# MCU_Core.net
KiCad netlist of a schematic drawn in Altium Designer
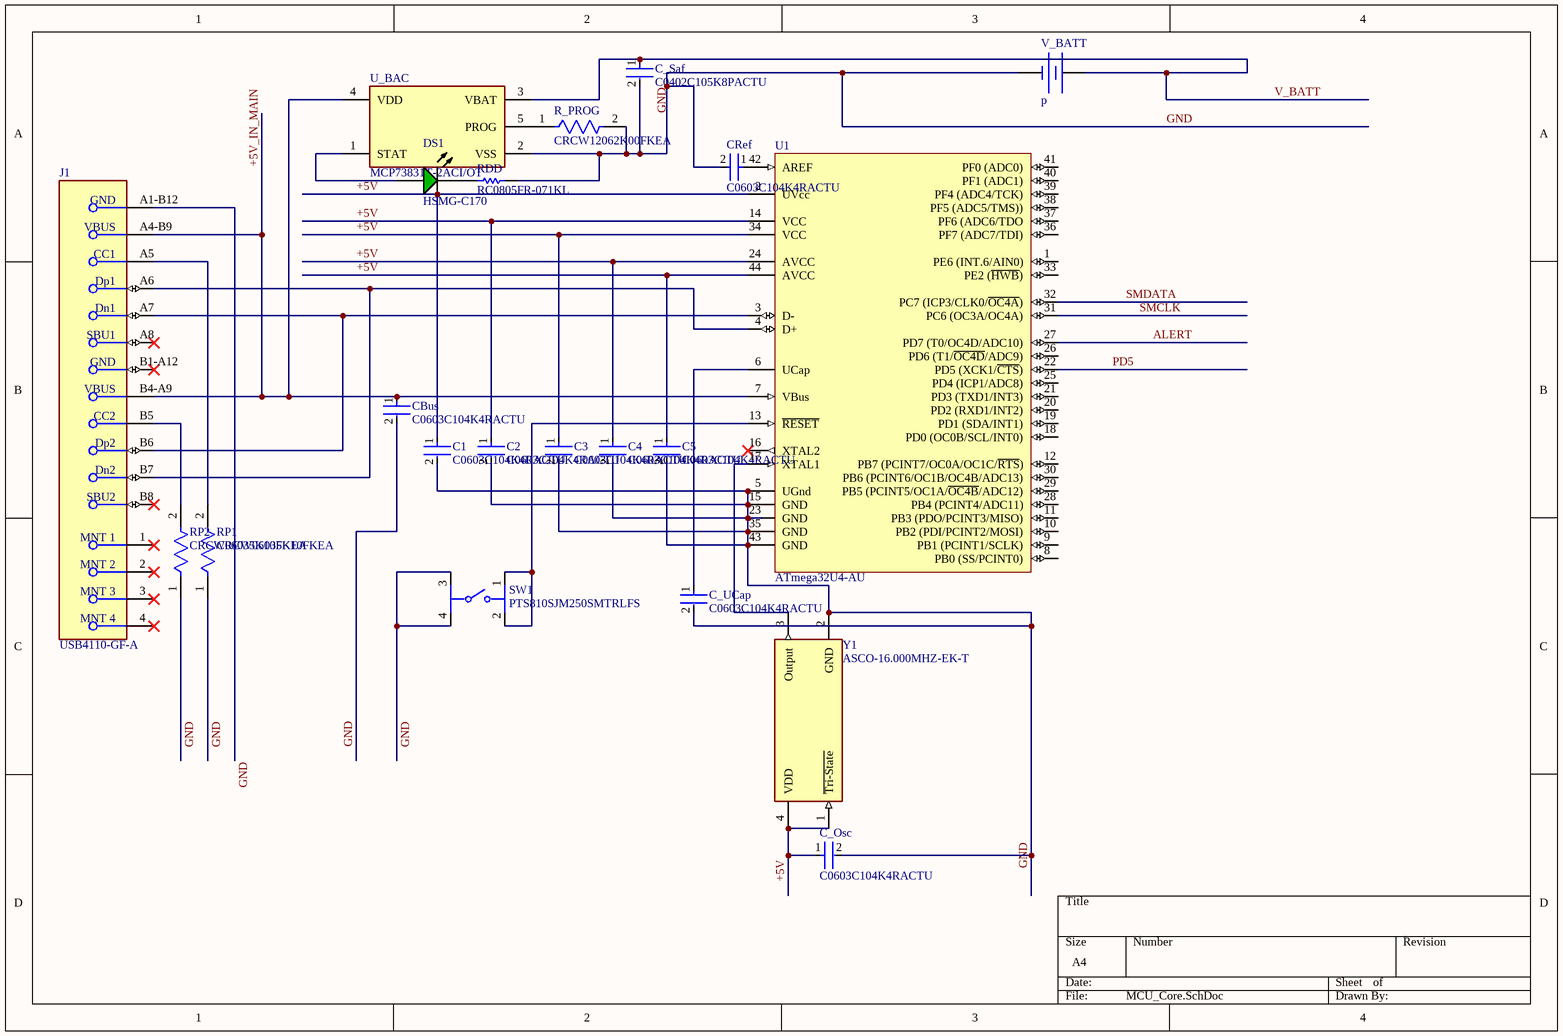
[diagram p0: MCU_Core.SchDoc]

(export (version "E")
  (design (tool "Eeschema 10.0.6"))
  (components
    (comp (ref "C1")
      (value "C0603C104K4RACTU")
      (footprint "FP-C0603C-CF-MFG")
      (description "Capacitor; Ceramic; Cap; .100uF; Tol 10%; SMT; Vol-Rtg 16V; X7R; Tape and Reel")
      (fields
        (field (name "OCTOPART") "https://octopart.com/c0603c104k4ractu-kemet-93067")
        (field (name "MANUFACTURER") "KEMET")
      )
      (libsource (lib "Altium Content Vault") (part "b4654b650e69147ec39a6b967a45e02"))
    )
    (comp (ref "C2")
      (value "C0603C104K4RACTU")
      (footprint "FP-C0603C-CF-MFG")
      (description "Capacitor; Ceramic; Cap; .100uF; Tol 10%; SMT; Vol-Rtg 16V; X7R; Tape and Reel")
      (fields
        (field (name "OCTOPART") "https://octopart.com/c0603c104k4ractu-kemet-93067")
        (field (name "MANUFACTURER") "KEMET")
      )
      (libsource (lib "Altium Content Vault") (part "b4654b650e69147ec39a6b967a45e02"))
    )
    (comp (ref "C3")
      (value "C0603C104K4RACTU")
      (footprint "FP-C0603C-CF-MFG")
      (description "Capacitor; Ceramic; Cap; .100uF; Tol 10%; SMT; Vol-Rtg 16V; X7R; Tape and Reel")
      (fields
        (field (name "OCTOPART") "https://octopart.com/c0603c104k4ractu-kemet-93067")
        (field (name "MANUFACTURER") "KEMET")
      )
      (libsource (lib "Altium Content Vault") (part "b4654b650e69147ec39a6b967a45e02"))
    )
    (comp (ref "C4")
      (value "C0603C104K4RACTU")
      (footprint "FP-C0603C-CF-MFG")
      (description "Capacitor; Ceramic; Cap; .100uF; Tol 10%; SMT; Vol-Rtg 16V; X7R; Tape and Reel")
      (fields
        (field (name "OCTOPART") "https://octopart.com/c0603c104k4ractu-kemet-93067")
        (field (name "MANUFACTURER") "KEMET")
      )
      (libsource (lib "Altium Content Vault") (part "b4654b650e69147ec39a6b967a45e02"))
    )
    (comp (ref "C5")
      (value "C0603C104K4RACTU")
      (footprint "FP-C0603C-CF-MFG")
      (description "Capacitor; Ceramic; Cap; .100uF; Tol 10%; SMT; Vol-Rtg 16V; X7R; Tape and Reel")
      (fields
        (field (name "OCTOPART") "https://octopart.com/c0603c104k4ractu-kemet-93067")
        (field (name "MANUFACTURER") "KEMET")
      )
      (libsource (lib "Altium Content Vault") (part "b4654b650e69147ec39a6b967a45e02"))
    )
    (comp (ref "CBus")
      (value "C0603C104K4RACTU")
      (footprint "FP-C0603C-CF-MFG")
      (description "Capacitor; Ceramic; Cap; .100uF; Tol 10%; SMT; Vol-Rtg 16V; X7R; Tape and Reel")
      (fields
        (field (name "OCTOPART") "https://octopart.com/c0603c104k4ractu-kemet-93067")
        (field (name "MANUFACTURER") "KEMET")
      )
      (libsource (lib "Altium Content Vault") (part "b4654b650e69147ec39a6b967a45e02"))
    )
    (comp (ref "CRef")
      (value "C0603C104K4RACTU")
      (footprint "FP-C0603C-CF-MFG")
      (description "Capacitor; Ceramic; Cap; .100uF; Tol 10%; SMT; Vol-Rtg 16V; X7R; Tape and Reel")
      (fields
        (field (name "OCTOPART") "https://octopart.com/c0603c104k4ractu-kemet-93067")
        (field (name "MANUFACTURER") "KEMET")
      )
      (libsource (lib "Altium Content Vault") (part "b4654b650e69147ec39a6b967a45e02"))
    )
    (comp (ref "C_Osc")
      (value "C0603C104K4RACTU")
      (footprint "FP-C0603C-CF-MFG")
      (description "Capacitor; Ceramic; Cap; .100uF; Tol 10%; SMT; Vol-Rtg 16V; X7R; Tape and Reel")
      (fields
        (field (name "OCTOPART") "https://octopart.com/c0603c104k4ractu-kemet-93067")
        (field (name "MANUFACTURER") "KEMET")
      )
      (libsource (lib "Altium Content Vault") (part "b4654b650e69147ec39a6b967a45e02"))
    )
    (comp (ref "C_Saf")
      (value "C0402C105K8PACTU")
      (footprint "FP-C0402C105K8PACTU-MFG")
      (description "CAP CER 1UF 10V X5R 0402")
      (fields (field (name "VOLTAGE") "10V") (field (name "TOLERANCE") "10%"))
      (libsource (lib "Altium Content Vault") (part "11868f565c42a9108669ba33697ecf6"))
    )
    (comp (ref "C_UCap")
      (value "C0603C104K4RACTU")
      (footprint "FP-C0603C-CF-MFG")
      (description "Capacitor; Ceramic; Cap; .100uF; Tol 10%; SMT; Vol-Rtg 16V; X7R; Tape and Reel")
      (fields
        (field (name "OCTOPART") "https://octopart.com/c0603c104k4ractu-kemet-93067")
        (field (name "MANUFACTURER") "KEMET")
      )
      (libsource (lib "Altium Content Vault") (part "b4654b650e69147ec39a6b967a45e02"))
    )
    (comp (ref "DS1")
      (value "HSMG-C170")
      (footprint "AVAG-HSMX-C170_V")
      (description "Chip LED, Green, 2.2 V, -40 to 85 degC, 2-Pin SMD, Pb-Free, Tape and Reel")
      (fields (field (name "MANUFACTURER") "Avago"))
      (libsource (lib "Altium Content Vault") (part "LED_GREEN_A1K2-2"))
    )
    (comp (ref "J1")
      (value "USB4110-GF-A")
      (footprint "FP-USB4110-GF-A-MFG")
      (description "CONN USB 2.0 TYPE-C R/A SMT")
      (fields
        (field (name "OCTOPART") "https://octopart.com/usb4110-gf-a-gct-103941985")
        (field (name "MANUFACTURER") "GCT")
      )
      (libsource (lib "Altium Content Vault") (part "e23f2b38bb3c3f98e683ebab9ede730"))
    )
    (comp (ref "RDD")
      (value "RC0805FR-071KL")
      (footprint "RESC2013X60X35ML10T20")
      (description "Chip Resistor, 1 KOhm, +/- 1%, 125 mW, -55 to 155 degC, 0805 (2012 Metric), RoHS, Tape and Reel")
      (fields (field (name "TOLERANCE") "1%") (field (name "MANUFACTURER") "Yageo"))
      (libsource (lib "Altium Content Vault") (part "RES-2"))
    )
    (comp (ref "RP1")
      (value "CRCW06035K10FKEA")
      (footprint "FP-CRCW0603-e3-IPC_C")
      (description "RES Thick Film, 5.1kΩ, 1%, 0.1W, 100ppm/°C, 0603")
      (fields (field (name "TOLERANCE") "1%"))
      (libsource (lib "Altium Content Vault") (part "1029c3af85768c4190bb7ad29bc67b5"))
    )
    (comp (ref "RP2")
      (value "CRCW06035K10FKEA")
      (footprint "FP-CRCW0603-e3-IPC_C")
      (description "RES Thick Film, 5.1kΩ, 1%, 0.1W, 100ppm/°C, 0603")
      (fields (field (name "TOLERANCE") "1%"))
      (libsource (lib "Altium Content Vault") (part "1029c3af85768c4190bb7ad29bc67b5"))
    )
    (comp (ref "R_PROG")
      (value "CRCW12062K00FKEA")
      (footprint "FP-CRCW1206-e3-IPC_A")
      (description "RES Thick Film, 2kΩ, 1%, 0.25W, 100ppm/°C, 1206")
      (fields (field (name "TOLERANCE") "1%"))
      (libsource (lib "Altium Content Vault") (part "1029c3af85768c4190bb7ad29bc67b5"))
    )
    (comp (ref "SW1")
      (value "PTS810SJM250SMTRLFS")
      (footprint "FP-PTS810SJM250SMTRLFS-MFG")
      (description "SWITCH TACTILE SPST-NO 0.05A 16V")
      (libsource (lib "Altium Content Vault") (part "1adf0dd01260c80cf25a44bfd6b99ba"))
    )
    (comp (ref "U1")
      (value "ATmega32U4-AU")
      (footprint "44ML_M")
      (libsource (lib "Altium Content Vault") (part "MC-8B-ATM16U4-SQ44"))
    )
    (comp (ref "U_BAC")
      (value "MCP73831T-2ACI/OT")
      (footprint "FP-C04-091-OT-IPC_B")
      (description "IC CONTROLLR LI-ION 4.2V SOT23-5")
      (libsource (lib "Altium Content Vault") (part "61f5a3bb3429d9e0caadea342aa3b19"))
    )
    (comp (ref "V_BATT")
      (value "Constant Voltage Source")
      (fields (field (name "DC MAGNITUDE") "p"))
      (libsource (lib "Simulation Generic Components") (part "Battery"))
    )
    (comp (ref "Y1")
      (value "ASCO-16.000MHZ-EK-T")
      (footprint "FP-ASCO-MFG")
      (description "Crystal Oscillator 16MHz ±30ppm CMOS 3.3V SMD 1.6x1.2mm")
      (libsource (lib "Altium Content Vault") (part "19c86ddd388e3e1e7fc069bbae5e46a"))
    )
  )
  (nets
    (net (code "1") (name "/+5V") (class "Default")
      (node (ref "C1") (pin "1") (pinfunction "1_1") (pintype "passive"))
      (node (ref "C2") (pin "1") (pinfunction "1_1") (pintype "passive"))
      (node (ref "C3") (pin "1") (pinfunction "1_1") (pintype "passive"))
      (node (ref "C4") (pin "1") (pinfunction "1_1") (pintype "passive"))
      (node (ref "C5") (pin "1") (pinfunction "1_1") (pintype "passive"))
      (node (ref "C_Osc") (pin "1") (pinfunction "1_1") (pintype "passive"))
      (node (ref "U1") (pin "14") (pinfunction "VCC_14") (pintype "power_in"))
      (node (ref "U1") (pin "2") (pinfunction "UVcc_2") (pintype "power_in"))
      (node (ref "U1") (pin "24") (pinfunction "AVCC_24") (pintype "power_in"))
      (node (ref "U1") (pin "34") (pinfunction "VCC_34") (pintype "power_in"))
      (node (ref "U1") (pin "44") (pinfunction "AVCC_44") (pintype "power_in"))
      (node (ref "Y1") (pin "1") (pinfunction "~{Tri-State}_1") (pintype "input"))
      (node (ref "Y1") (pin "4") (pinfunction "VDD_4") (pintype "power_in"))
    )
    (net (code "2") (name "/+5V_IN_MAIN") (class "Default")
      (node (ref "CBus") (pin "1") (pinfunction "1_1") (pintype "passive"))
      (node (ref "J1") (pin "A4-B9") (pinfunction "VBUS_A4-B9") (pintype "power_in"))
      (node (ref "J1") (pin "B4-A9") (pinfunction "VBUS_B4-A9") (pintype "power_in"))
      (node (ref "U1") (pin "7") (pinfunction "VBus_7") (pintype "input"))
      (node (ref "U_BAC") (pin "4") (pinfunction "VDD_4") (pintype "power_in"))
    )
    (net (code "3") (name "/ALERT") (class "Default")
      (node (ref "U1") (pin "27") (pinfunction "PD7_(T0/OC4D/ADC10)_27") (pintype "bidirectional"))
    )
    (net (code "4") (name "/GND") (class "Default")
      (node (ref "C1") (pin "2") (pinfunction "2_2") (pintype "passive"))
      (node (ref "C2") (pin "2") (pinfunction "2_2") (pintype "passive"))
      (node (ref "C3") (pin "2") (pinfunction "2_2") (pintype "passive"))
      (node (ref "C4") (pin "2") (pinfunction "2_2") (pintype "passive"))
      (node (ref "C5") (pin "2") (pinfunction "2_2") (pintype "passive"))
      (node (ref "CBus") (pin "2") (pinfunction "2_2") (pintype "passive"))
      (node (ref "CRef") (pin "2") (pinfunction "2_2") (pintype "passive"))
      (node (ref "C_Osc") (pin "2") (pinfunction "2_2") (pintype "passive"))
      (node (ref "C_Saf") (pin "2") (pinfunction "2_2") (pintype "passive"))
      (node (ref "C_UCap") (pin "2") (pinfunction "2_2") (pintype "passive"))
      (node (ref "J1") (pin "A1-B12") (pinfunction "GND_A1-B12") (pintype "passive"))
      (node (ref "RDD") (pin "2") (pinfunction "2_2") (pintype "passive"))
      (node (ref "RP1") (pin "1") (pinfunction "1_1") (pintype "passive"))
      (node (ref "RP2") (pin "1") (pinfunction "1_1") (pintype "passive"))
      (node (ref "R_PROG") (pin "2") (pinfunction "2_2") (pintype "passive"))
      (node (ref "SW1") (pin "3") (pinfunction "3_3") (pintype "passive"))
      (node (ref "SW1") (pin "4") (pinfunction "4_4") (pintype "passive"))
      (node (ref "U1") (pin "15") (pinfunction "GND_15") (pintype "power_in"))
      (node (ref "U1") (pin "23") (pinfunction "GND_23") (pintype "power_in"))
      (node (ref "U1") (pin "35") (pinfunction "GND_35") (pintype "power_in"))
      (node (ref "U1") (pin "43") (pinfunction "GND_43") (pintype "power_in"))
      (node (ref "U1") (pin "5") (pinfunction "UGnd_5") (pintype "power_in"))
      (node (ref "U_BAC") (pin "2") (pinfunction "VSS_2") (pintype "power_in"))
      (node (ref "V_BATT") (pin "2") (pinfunction "2_2") (pintype "passive"))
      (node (ref "Y1") (pin "2") (pinfunction "GND_2") (pintype "power_in"))
    )
    (net (code "5") (name "/PD5") (class "Default")
      (node (ref "U1") (pin "22") (pinfunction "PD5_(XCK1/~{CTS})_22") (pintype "bidirectional"))
    )
    (net (code "6") (name "/SMCLK") (class "Default")
      (node (ref "U1") (pin "31") (pinfunction "PC6_(OC3A/OC4A)_31") (pintype "bidirectional"))
    )
    (net (code "7") (name "/SMDATA") (class "Default")
      (node (ref "U1") (pin "32") (pinfunction "PC7_(ICP3/CLK0/~{OC4A})_32") (pintype "bidirectional"))
    )
    (net (code "8") (name "/V_BATT") (class "Default")
      (node (ref "C_Saf") (pin "1") (pinfunction "1_1") (pintype "passive"))
      (node (ref "U_BAC") (pin "3") (pinfunction "VBAT_3") (pintype "power_in"))
      (node (ref "V_BATT") (pin "1") (pinfunction "1_1") (pintype "passive"))
    )
    (net (code "9") (name "Net-(DS1-A)") (class "Default")
      (node (ref "DS1") (pin "1") (pinfunction "A_1") (pintype "passive"))
      (node (ref "U_BAC") (pin "1") (pinfunction "STAT_1") (pintype "passive"))
    )
    (net (code "10") (name "Net-(DS1-K)") (class "Default")
      (node (ref "DS1") (pin "2") (pinfunction "K_2") (pintype "passive"))
      (node (ref "RDD") (pin "1") (pinfunction "1_1") (pintype "passive"))
    )
    (net (code "11") (name "Net-(J1-CC1)") (class "Default")
      (node (ref "J1") (pin "A5") (pinfunction "CC1_A5") (pintype "power_in"))
      (node (ref "RP1") (pin "2") (pinfunction "2_2") (pintype "passive"))
    )
    (net (code "12") (name "Net-(J1-CC2)") (class "Default")
      (node (ref "J1") (pin "B5") (pinfunction "CC2_B5") (pintype "power_in"))
      (node (ref "RP2") (pin "2") (pinfunction "2_2") (pintype "passive"))
    )
    (net (code "13") (name "Net-(J1-Dn1)") (class "Default")
      (node (ref "J1") (pin "A7") (pinfunction "Dn1_A7") (pintype "bidirectional"))
      (node (ref "J1") (pin "B6") (pinfunction "Dp2_B6") (pintype "bidirectional"))
      (node (ref "U1") (pin "3") (pinfunction "D-_3") (pintype "bidirectional"))
    )
    (net (code "14") (name "Net-(J1-Dn2)") (class "Default")
      (node (ref "J1") (pin "A6") (pinfunction "Dp1_A6") (pintype "bidirectional"))
      (node (ref "J1") (pin "B7") (pinfunction "Dn2_B7") (pintype "bidirectional"))
      (node (ref "U1") (pin "4") (pinfunction "D+_4") (pintype "bidirectional"))
    )
    (net (code "15") (name "Net-(U1-AREF)") (class "Default")
      (node (ref "CRef") (pin "1") (pinfunction "1_1") (pintype "passive"))
      (node (ref "U1") (pin "42") (pinfunction "AREF_42") (pintype "input"))
    )
    (net (code "16") (name "Net-(U1-UCap)") (class "Default")
      (node (ref "C_UCap") (pin "1") (pinfunction "1_1") (pintype "passive"))
      (node (ref "U1") (pin "6") (pinfunction "UCap_6") (pintype "passive"))
    )
    (net (code "17") (name "Net-(U1-XTAL1)") (class "Default")
      (node (ref "U1") (pin "17") (pinfunction "XTAL1_17") (pintype "input"))
      (node (ref "Y1") (pin "3") (pinfunction "Output_3") (pintype "output"))
    )
    (net (code "18") (name "Net-(U1-~{RESET})") (class "Default")
      (node (ref "SW1") (pin "1") (pinfunction "1_1") (pintype "passive"))
      (node (ref "SW1") (pin "2") (pinfunction "2_2") (pintype "passive"))
      (node (ref "U1") (pin "13") (pinfunction "~{RESET}_13") (pintype "input"))
    )
    (net (code "19") (name "Net-(U_BAC-PROG)") (class "Default")
      (node (ref "R_PROG") (pin "1") (pinfunction "1_1") (pintype "passive"))
      (node (ref "U_BAC") (pin "5") (pinfunction "PROG_5") (pintype "passive"))
    )
    (net (code "20") (name "unconnected-(J1-GND-PadB1-A12)") (class "Default")
      (node (ref "J1") (pin "B1-A12") (pinfunction "GND_B1-A12") (pintype "bidirectional+no_connect"))
    )
    (net (code "21") (name "unconnected-(J1-MNT_1-Pad1)") (class "Default")
      (node (ref "J1") (pin "1") (pinfunction "MNT_1_1") (pintype "passive+no_connect"))
    )
    (net (code "22") (name "unconnected-(J1-MNT_2-Pad2)") (class "Default")
      (node (ref "J1") (pin "2") (pinfunction "MNT_2_2") (pintype "passive+no_connect"))
    )
    (net (code "23") (name "unconnected-(J1-MNT_3-Pad3)") (class "Default")
      (node (ref "J1") (pin "3") (pinfunction "MNT_3_3") (pintype "passive+no_connect"))
    )
    (net (code "24") (name "unconnected-(J1-MNT_4-Pad4)") (class "Default")
      (node (ref "J1") (pin "4") (pinfunction "MNT_4_4") (pintype "passive+no_connect"))
    )
    (net (code "25") (name "unconnected-(J1-SBU1-PadA8)") (class "Default")
      (node (ref "J1") (pin "A8") (pinfunction "SBU1_A8") (pintype "bidirectional+no_connect"))
    )
    (net (code "26") (name "unconnected-(J1-SBU2-PadB8)") (class "Default")
      (node (ref "J1") (pin "B8") (pinfunction "SBU2_B8") (pintype "bidirectional+no_connect"))
    )
    (net (code "27") (name "unconnected-(U1-PB0_(SS{slash}PCINT0)-Pad8)") (class "Default")
      (node (ref "U1") (pin "8") (pinfunction "PB0_(SS/PCINT0)_8") (pintype "bidirectional"))
    )
    (net (code "28") (name "unconnected-(U1-PB1_(PCINT1{slash}SCLK)-Pad9)") (class "Default")
      (node (ref "U1") (pin "9") (pinfunction "PB1_(PCINT1/SCLK)_9") (pintype "bidirectional"))
    )
    (net (code "29") (name "unconnected-(U1-PB2_(PDI{slash}PCINT2{slash}MOSI)-Pad10)") (class "Default")
      (node (ref "U1") (pin "10") (pinfunction "PB2_(PDI/PCINT2/MOSI)_10") (pintype "bidirectional"))
    )
    (net (code "30") (name "unconnected-(U1-PB3_(PDO{slash}PCINT3{slash}MISO)-Pad11)") (class "Default")
      (node (ref "U1") (pin "11") (pinfunction "PB3_(PDO/PCINT3/MISO)_11") (pintype "bidirectional"))
    )
    (net (code "31") (name "unconnected-(U1-PB4_(PCINT4{slash}ADC11)-Pad28)") (class "Default")
      (node (ref "U1") (pin "28") (pinfunction "PB4_(PCINT4/ADC11)_28") (pintype "bidirectional"))
    )
    (net (code "32") (name "unconnected-(U1-PB5_(PCINT5{slash}OC1A{slash}~{OC4B}{slash}ADC12)-Pad29)") (class "Default")
      (node (ref "U1") (pin "29") (pinfunction "PB5_(PCINT5/OC1A/~{OC4B}/ADC12)_29") (pintype "bidirectional"))
    )
    (net (code "33") (name "unconnected-(U1-PB6_(PCINT6{slash}OC1B{slash}OC4B{slash}ADC13)-Pad30)") (class "Default")
      (node (ref "U1") (pin "30") (pinfunction "PB6_(PCINT6/OC1B/OC4B/ADC13)_30") (pintype "bidirectional"))
    )
    (net (code "34") (name "unconnected-(U1-PB7_(PCINT7{slash}OC0A{slash}OC1C{slash}~{RTS})-Pad12)") (class "Default")
      (node (ref "U1") (pin "12") (pinfunction "PB7_(PCINT7/OC0A/OC1C/~{RTS})_12") (pintype "bidirectional"))
    )
    (net (code "35") (name "unconnected-(U1-PD0_(OC0B{slash}SCL{slash}INT0)-Pad18)") (class "Default")
      (node (ref "U1") (pin "18") (pinfunction "PD0_(OC0B/SCL/INT0)_18") (pintype "bidirectional"))
    )
    (net (code "36") (name "unconnected-(U1-PD1_(SDA{slash}INT1)-Pad19)") (class "Default")
      (node (ref "U1") (pin "19") (pinfunction "PD1_(SDA/INT1)_19") (pintype "bidirectional"))
    )
    (net (code "37") (name "unconnected-(U1-PD2_(RXD1{slash}INT2)-Pad20)") (class "Default")
      (node (ref "U1") (pin "20") (pinfunction "PD2_(RXD1/INT2)_20") (pintype "bidirectional"))
    )
    (net (code "38") (name "unconnected-(U1-PD3_(TXD1{slash}INT3)-Pad21)") (class "Default")
      (node (ref "U1") (pin "21") (pinfunction "PD3_(TXD1/INT3)_21") (pintype "bidirectional"))
    )
    (net (code "39") (name "unconnected-(U1-PD4_(ICP1{slash}ADC8)-Pad25)") (class "Default")
      (node (ref "U1") (pin "25") (pinfunction "PD4_(ICP1/ADC8)_25") (pintype "bidirectional"))
    )
    (net (code "40") (name "unconnected-(U1-PD6_(T1{slash}~{OC4D}{slash}ADC9)-Pad26)") (class "Default")
      (node (ref "U1") (pin "26") (pinfunction "PD6_(T1/~{OC4D}/ADC9)_26") (pintype "bidirectional"))
    )
    (net (code "41") (name "unconnected-(U1-PE2_(~{HWB})-Pad33)") (class "Default")
      (node (ref "U1") (pin "33") (pinfunction "PE2_(~{HWB})_33") (pintype "bidirectional"))
    )
    (net (code "42") (name "unconnected-(U1-PE6_(INT.6{slash}AIN0)-Pad1)") (class "Default")
      (node (ref "U1") (pin "1") (pinfunction "PE6_(INT.6/AIN0)_1") (pintype "bidirectional"))
    )
    (net (code "43") (name "unconnected-(U1-PF0_(ADC0)-Pad41)") (class "Default")
      (node (ref "U1") (pin "41") (pinfunction "PF0_(ADC0)_41") (pintype "bidirectional"))
    )
    (net (code "44") (name "unconnected-(U1-PF1_(ADC1)-Pad40)") (class "Default")
      (node (ref "U1") (pin "40") (pinfunction "PF1_(ADC1)_40") (pintype "bidirectional"))
    )
    (net (code "45") (name "unconnected-(U1-PF4_(ADC4{slash}TCK)-Pad39)") (class "Default")
      (node (ref "U1") (pin "39") (pinfunction "PF4_(ADC4/TCK)_39") (pintype "bidirectional"))
    )
    (net (code "46") (name "unconnected-(U1-PF5_(ADC5{slash}TMS))-Pad38)") (class "Default")
      (node (ref "U1") (pin "38") (pinfunction "PF5_(ADC5/TMS))_38") (pintype "bidirectional"))
    )
    (net (code "47") (name "unconnected-(U1-PF6_(ADC6{slash}TDO-Pad37)") (class "Default")
      (node (ref "U1") (pin "37") (pinfunction "PF6_(ADC6/TDO_37") (pintype "bidirectional"))
    )
    (net (code "48") (name "unconnected-(U1-PF7_(ADC7{slash}TDI)-Pad36)") (class "Default")
      (node (ref "U1") (pin "36") (pinfunction "PF7_(ADC7/TDI)_36") (pintype "bidirectional"))
    )
    (net (code "49") (name "unconnected-(U1-XTAL2-Pad16)") (class "Default")
      (node (ref "U1") (pin "16") (pinfunction "XTAL2_16") (pintype "output+no_connect"))
    )
  )
)
